# Display.net
KiCad netlist of a schematic drawn in Altium Designer
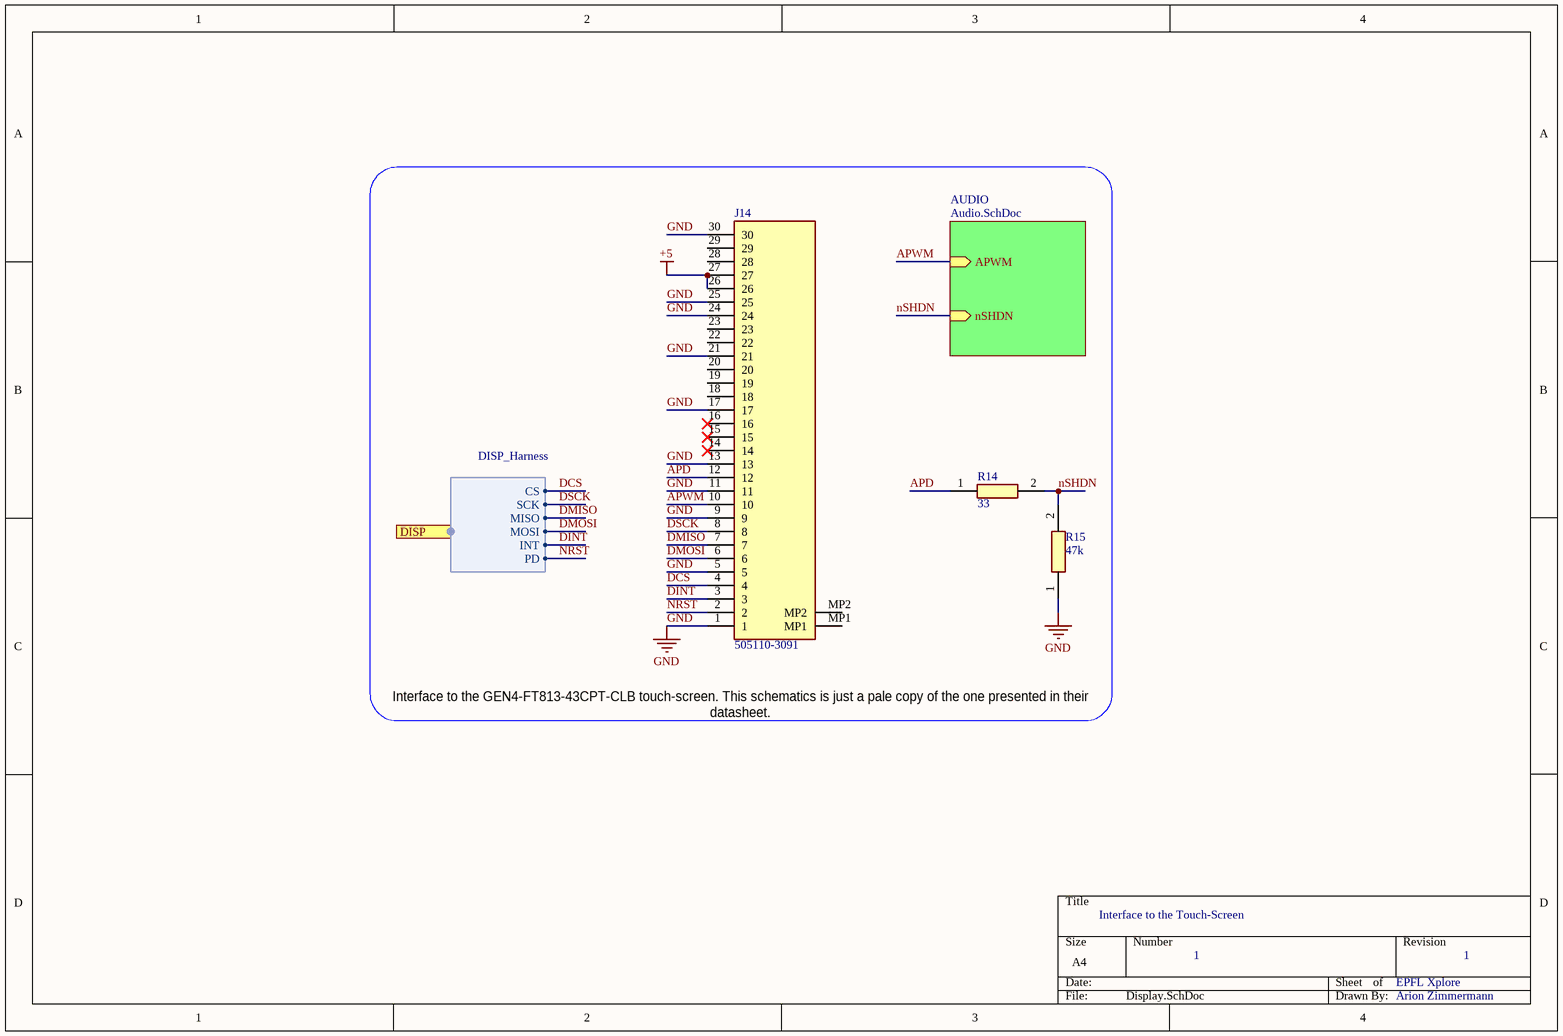
[diagram p0: Display.SchDoc]

(export (version "E")
  (design (tool "Eeschema 10.0.6"))
  (components
    (comp (ref "J14")
      (value "505110-3091")
      (footprint "5051103091")
      (description "Connector")
      (fields (field (name "MOUSER PART NUMBER") "538-505110-3091"))
      (libsource (lib "*") (part "505110-3091"))
    )
    (comp (ref "R14")
      (value "33")
      (footprint "SamacSys:RESC1608X50N")
      (description "Resistor")
      (fields
        (field (name "MANUFACTURER_PART_NUMBER") "CRCW0603787RFKEA")
        (field (name "Comment") "CRCW060333R0JNEAC")
      )
      (libsource (lib "CarrierBoard") (part "CRCW0603931RFKEA"))
    )
    (comp (ref "R15")
      (value "47k")
      (footprint "SamacSys:RESC1608X50N")
      (description "Resistor")
      (fields
        (field (name "MANUFACTURER_PART_NUMBER") "CRCW0603787RFKEA")
        (field (name "Comment") "CRCW060347K0FKEAC")
      )
      (libsource (lib "") (part "CRCW0603931RFKEA_1"))
    )
  )
  (nets
    (net (code "2") (name "+5") (class "Default")
      (node (ref "J14") (pin "26") (pinfunction "26_26") (pintype "passive"))
      (node (ref "J14") (pin "27") (pinfunction "27_27") (pintype "passive"))
    )
    (net (code "3") (name "/APD") (class "Default")
      (node (ref "J14") (pin "12") (pinfunction "12_12") (pintype "passive"))
      (node (ref "R14") (pin "1") (pinfunction "1_1") (pintype "passive"))
    )
    (net (code "4") (name "/APWM") (class "Default")
      (node (ref "J14") (pin "10") (pinfunction "10_10") (pintype "passive"))
    )
    (net (code "5") (name "/DCS") (class "Default")
      (node (ref "J14") (pin "4") (pinfunction "4_4") (pintype "passive"))
    )
    (net (code "6") (name "/DINT") (class "Default")
      (node (ref "J14") (pin "3") (pinfunction "3_3") (pintype "passive"))
    )
    (net (code "7") (name "/DMISO") (class "Default")
      (node (ref "J14") (pin "7") (pinfunction "7_7") (pintype "passive"))
    )
    (net (code "8") (name "/DMOSI") (class "Default")
      (node (ref "J14") (pin "6") (pinfunction "6_6") (pintype "passive"))
    )
    (net (code "9") (name "/DSCK") (class "Default")
      (node (ref "J14") (pin "8") (pinfunction "8_8") (pintype "passive"))
    )
    (net (code "10") (name "/NRST") (class "Default")
      (node (ref "J14") (pin "2") (pinfunction "2_2") (pintype "passive"))
    )
    (net (code "11") (name "/nSHDN") (class "Default")
      (node (ref "R14") (pin "2") (pinfunction "2_2") (pintype "passive"))
      (node (ref "R15") (pin "2") (pinfunction "2_2") (pintype "passive"))
    )
    (net (code "13") (name "GND") (class "Default")
      (node (ref "J14") (pin "1") (pinfunction "1_1") (pintype "passive"))
      (node (ref "J14") (pin "11") (pinfunction "11_11") (pintype "passive"))
      (node (ref "J14") (pin "13") (pinfunction "13_13") (pintype "passive"))
      (node (ref "J14") (pin "17") (pinfunction "17_17") (pintype "passive"))
      (node (ref "J14") (pin "21") (pinfunction "21_21") (pintype "passive"))
      (node (ref "J14") (pin "24") (pinfunction "24_24") (pintype "passive"))
      (node (ref "J14") (pin "25") (pinfunction "25_25") (pintype "passive"))
      (node (ref "J14") (pin "30") (pinfunction "30_30") (pintype "passive"))
      (node (ref "J14") (pin "5") (pinfunction "5_5") (pintype "passive"))
      (node (ref "J14") (pin "9") (pinfunction "9_9") (pintype "passive"))
      (node (ref "R15") (pin "1") (pinfunction "1_1") (pintype "passive"))
    )
    (net (code "14") (name "unconnected-(J14-Pad14)") (class "Default")
      (node (ref "J14") (pin "14") (pinfunction "14_14") (pintype "passive+no_connect"))
    )
    (net (code "15") (name "unconnected-(J14-Pad15)") (class "Default")
      (node (ref "J14") (pin "15") (pinfunction "15_15") (pintype "passive+no_connect"))
    )
    (net (code "16") (name "unconnected-(J14-Pad16)") (class "Default")
      (node (ref "J14") (pin "16") (pinfunction "16_16") (pintype "passive+no_connect"))
    )
    (net (code "17") (name "unconnected-(J14-Pad18)") (class "Default")
      (node (ref "J14") (pin "18") (pinfunction "18_18") (pintype "passive"))
    )
    (net (code "18") (name "unconnected-(J14-Pad19)") (class "Default")
      (node (ref "J14") (pin "19") (pinfunction "19_19") (pintype "passive"))
    )
    (net (code "19") (name "unconnected-(J14-Pad20)") (class "Default")
      (node (ref "J14") (pin "20") (pinfunction "20_20") (pintype "passive"))
    )
    (net (code "20") (name "unconnected-(J14-Pad22)") (class "Default")
      (node (ref "J14") (pin "22") (pinfunction "22_22") (pintype "passive"))
    )
    (net (code "21") (name "unconnected-(J14-Pad23)") (class "Default")
      (node (ref "J14") (pin "23") (pinfunction "23_23") (pintype "passive"))
    )
    (net (code "22") (name "unconnected-(J14-Pad28)") (class "Default")
      (node (ref "J14") (pin "28") (pinfunction "28_28") (pintype "passive"))
    )
    (net (code "23") (name "unconnected-(J14-Pad29)") (class "Default")
      (node (ref "J14") (pin "29") (pinfunction "29_29") (pintype "passive"))
    )
    (net (code "24") (name "unconnected-(J14-PadMP1)") (class "Default")
      (node (ref "J14") (pin "MP1") (pinfunction "MP1_MP1") (pintype "passive"))
    )
    (net (code "25") (name "unconnected-(J14-PadMP2)") (class "Default")
      (node (ref "J14") (pin "MP2") (pinfunction "MP2_MP2") (pintype "passive"))
    )
  )
)
